# PICkit_Adapter.net
KiCad netlist of a schematic drawn in EAGLE
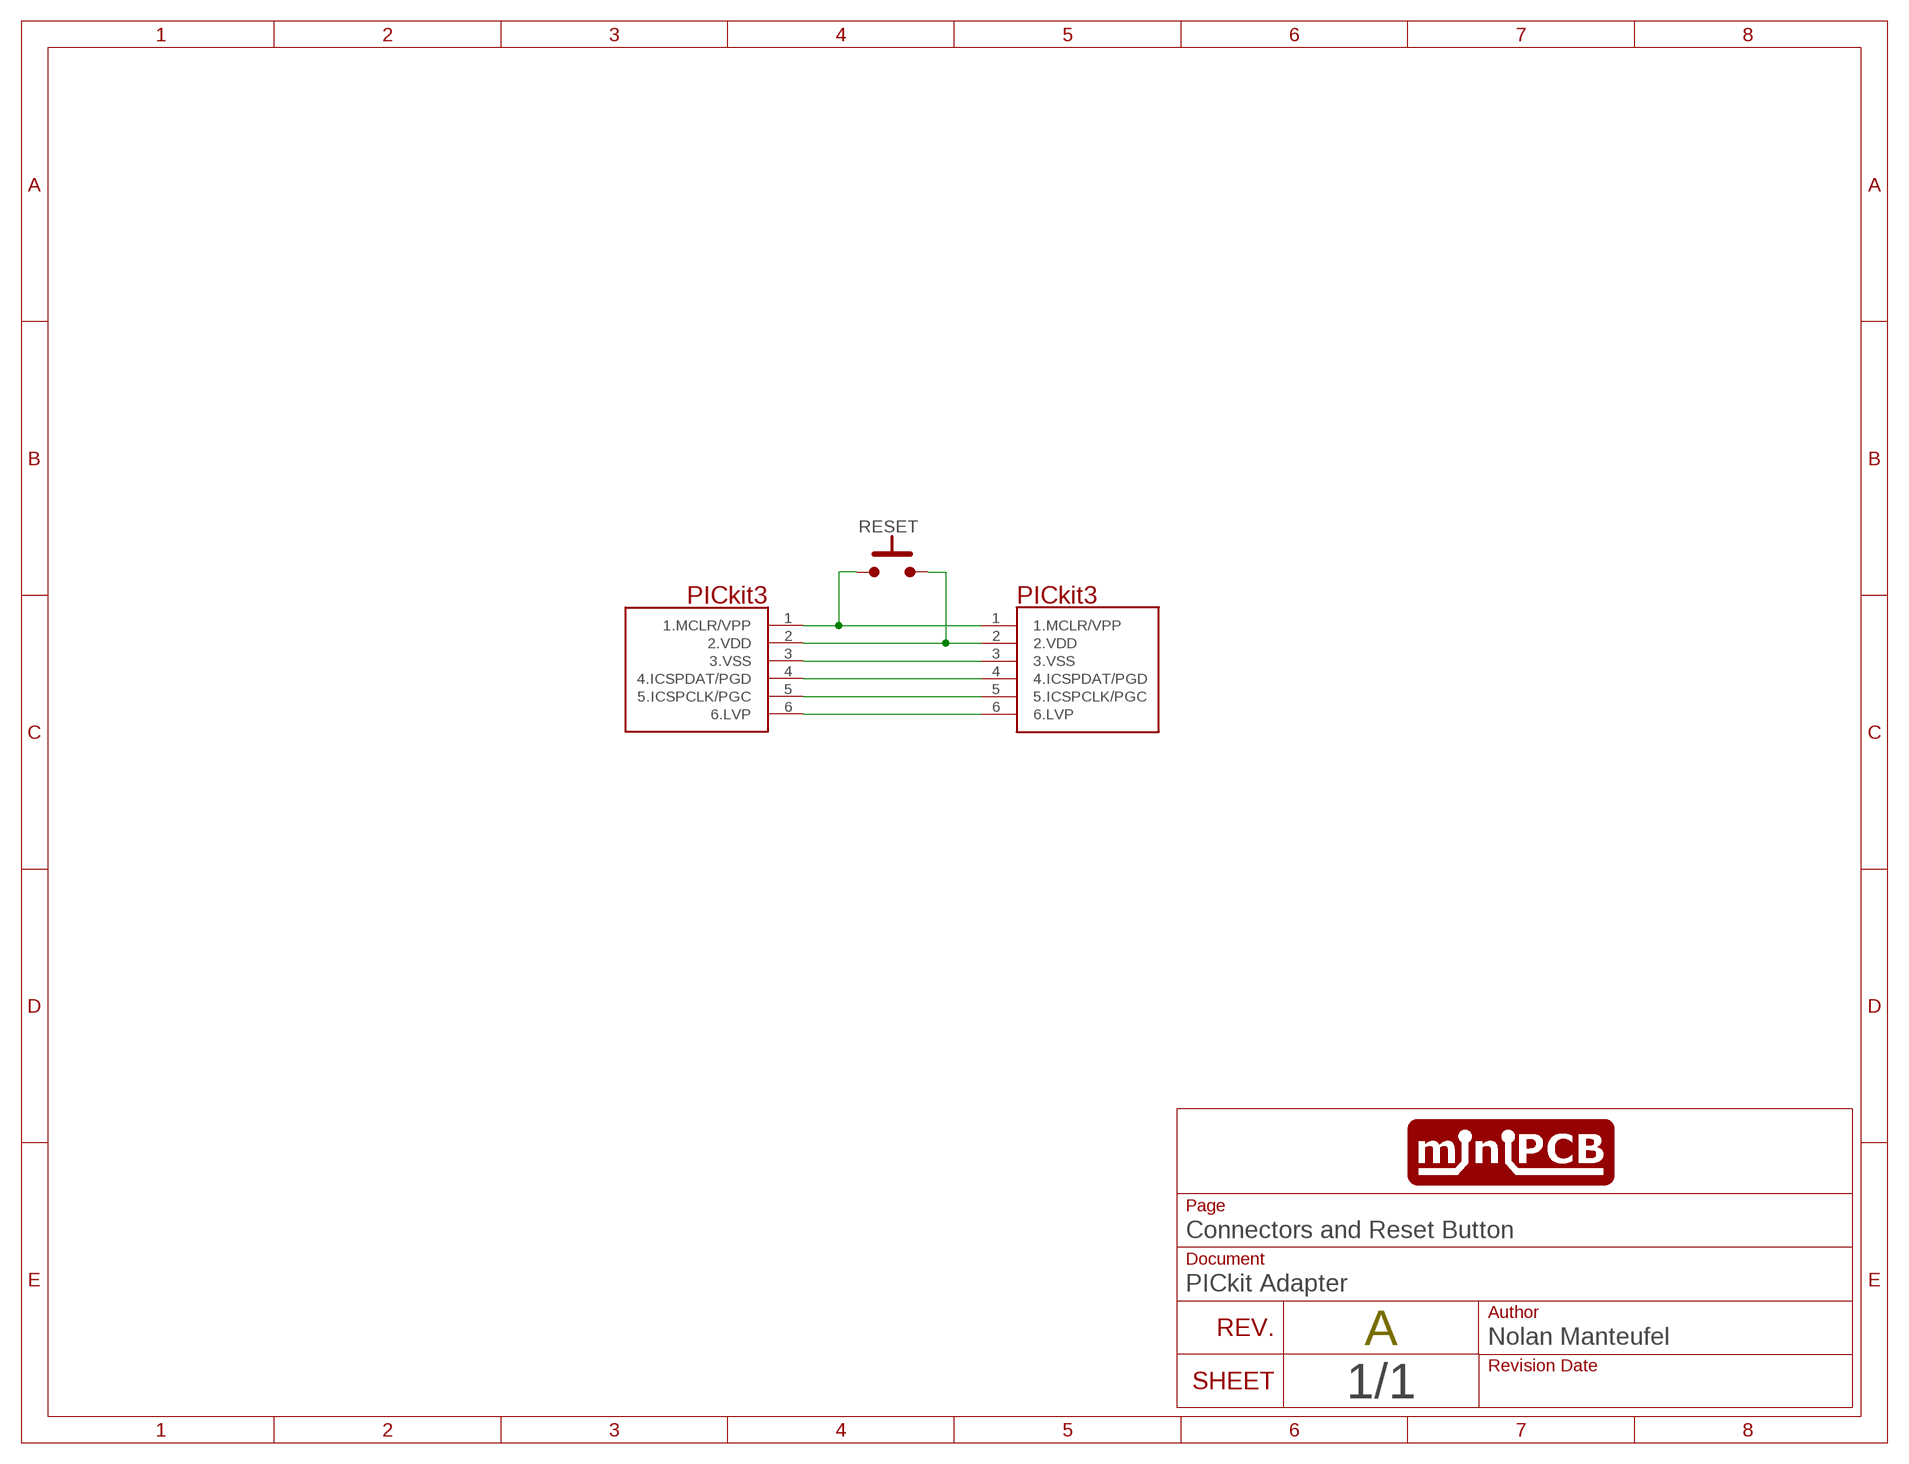
[diagram p0: schematic, sheet 1]

(export (version "E")
  (design (tool "Eeschema 10.0.6"))
  (components
    (comp (ref "RESET")
      (value "PUSHBUTTON3X6MM")
      (footprint "eagle-import:3X6MM")
      (libsource (lib "eagle-import") (part "PUSHBUTTON3X6MM"))
    )
    (comp (ref "U$2")
      (value "PICKIT3/1.27")
      (footprint "eagle-import:PINS_6_1MM27")
      (libsource (lib "eagle-import") (part "PICKIT3/1.27"))
    )
    (comp (ref "U$3")
      (value "PICKIT")
      (footprint "eagle-import:PINS_6_PICKIT3_TEXT")
      (libsource (lib "eagle-import") (part "PICKIT3TEXT"))
    )
  )
  (nets
    (net (code "1") (name "Net-(U$2-1.MCLR{slash}VPP)") (class "Default")
      (node (ref "RESET") (pin "1") (pinfunction "1_1") (pintype "bidirectional"))
      (node (ref "U$2") (pin "1") (pinfunction "1.MCLR/VPP_1") (pintype "bidirectional"))
      (node (ref "U$3") (pin "1") (pinfunction "1.MCLR/VPP_1") (pintype "bidirectional"))
    )
    (net (code "2") (name "Net-(U$2-2.VDD)") (class "Default")
      (node (ref "RESET") (pin "2") (pinfunction "2_2") (pintype "bidirectional"))
      (node (ref "U$2") (pin "2") (pinfunction "2.VDD_2") (pintype "bidirectional"))
      (node (ref "U$3") (pin "2") (pinfunction "2.VDD_2") (pintype "bidirectional"))
    )
    (net (code "3") (name "Net-(U$2-3.VSS)") (class "Default")
      (node (ref "U$2") (pin "3") (pinfunction "3.VSS_3") (pintype "bidirectional"))
      (node (ref "U$3") (pin "3") (pinfunction "3.VSS_3") (pintype "bidirectional"))
    )
    (net (code "4") (name "Net-(U$2-4.ICSPDAT{slash}PGD)") (class "Default")
      (node (ref "U$2") (pin "4") (pinfunction "4.ICSPDAT/PGD_4") (pintype "bidirectional"))
      (node (ref "U$3") (pin "4") (pinfunction "4.ICSPDAT/PGD_4") (pintype "bidirectional"))
    )
    (net (code "5") (name "Net-(U$2-5.ICSPCLK{slash}PGC)") (class "Default")
      (node (ref "U$2") (pin "5") (pinfunction "5.ICSPCLK/PGC_5") (pintype "bidirectional"))
      (node (ref "U$3") (pin "5") (pinfunction "5.ICSPCLK/PGC_5") (pintype "bidirectional"))
    )
    (net (code "6") (name "Net-(U$2-6.LVP)") (class "Default")
      (node (ref "U$2") (pin "6") (pinfunction "6.LVP_6") (pintype "bidirectional"))
      (node (ref "U$3") (pin "6") (pinfunction "6.LVP_6") (pintype "bidirectional"))
    )
  )
)
